# Power.net
KiCad netlist of a schematic drawn in Altium Designer
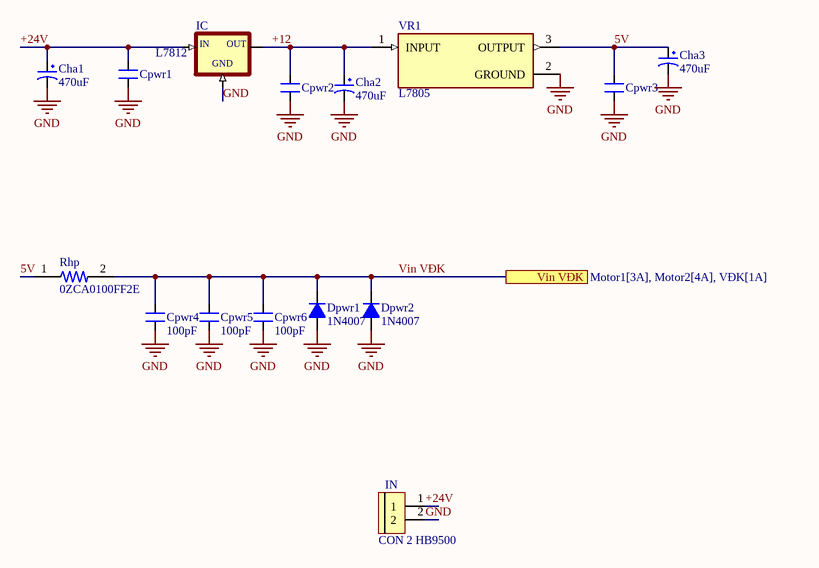
[diagram p0: Power.SchDoc]

(export (version "E")
  (design (tool "Eeschema 10.0.6"))
  (components
    (comp (ref "Cha1")
      (value "470uF")
      (footprint "CP1.5/3.4")
      (description "Cap 1000uF/16V - 220uF/50V")
      (libsource (lib "SCH_Lib_Devzone") (part "CP4"))
    )
    (comp (ref "Cha2")
      (value "470uF")
      (footprint "CP1.5/3.4")
      (description "Cap 1000uF/16V - 220uF/50V")
      (libsource (lib "SCH_Lib_Devzone") (part "CP4"))
    )
    (comp (ref "Cha3")
      (value "470uF")
      (footprint "CP1.5/3.4")
      (description "Cap 1000uF/16V - 220uF/50V")
      (libsource (lib "SCH_Lib_Devzone") (part "CP4"))
    )
    (comp (ref "Cpwr1")
      (value "100pF")
      (footprint "CN1")
      (description "Cap np  1pF - 472pF")
      (libsource (lib "SCH_Lib_Devzone") (part "CN1"))
    )
    (comp (ref "Cpwr2")
      (value "100pF")
      (footprint "CN1")
      (description "Cap np  1pF - 472pF")
      (libsource (lib "SCH_Lib_Devzone") (part "CN1"))
    )
    (comp (ref "Cpwr3")
      (value "100pF")
      (footprint "CN1")
      (description "Cap np  1pF - 472pF")
      (libsource (lib "SCH_Lib_Devzone") (part "CN1"))
    )
    (comp (ref "Cpwr4")
      (value "100pF")
      (footprint "CN1")
      (description "Cap np  1pF - 472pF")
      (libsource (lib "SCH_Lib_Devzone") (part "CN1"))
    )
    (comp (ref "Cpwr5")
      (value "100pF")
      (footprint "CN1")
      (description "Cap np  1pF - 472pF")
      (libsource (lib "SCH_Lib_Devzone") (part "CN1"))
    )
    (comp (ref "Cpwr6")
      (value "100pF")
      (footprint "CN1")
      (description "Cap np  1pF - 472pF")
      (libsource (lib "SCH_Lib_Devzone") (part "CN1"))
    )
    (comp (ref "Dpwr1")
      (value "1N4007")
      (footprint "D0.5A")
      (description "Diode 1A")
      (libsource (lib "SCH_Lib_Devzone") (part "D1A"))
    )
    (comp (ref "Dpwr2")
      (value "1N4007")
      (footprint "D0.5A")
      (description "Diode 1A")
      (libsource (lib "SCH_Lib_Devzone") (part "D1A"))
    )
    (comp (ref "IC")
      (value "L7812")
      (footprint "78XXS")
      (description "Linear Voltage Regulator IC 1 Output 1.5A D2PAK")
      (fields (field (name "MF") "STMicroelectronics"))
      (libsource (lib "L7812") (part "L7812"))
    )
    (comp (ref "IN")
      (value "CON 2 HB9500")
      (footprint "CON 2 HB9500")
      (description "Cắm")
      (libsource (lib "Altium_Lib_by_KhueNguyenCreator") (part "CON 2 HB9500"))
    )
    (comp (ref "Rhp")
      (value "0ZCA0100FF2E")
      (footprint "RESC3216X125N")
      (description "Polymeric PTC Resettable Fuse 6V 1 A Ih Surface Mount 1206 (3216 Metric), Concave")
      (fields (field (name "MF") "Bel Fuse"))
      (libsource (lib "0ZCA0100FF2E") (part "0ZCA0100FF2E"))
    )
    (comp (ref "VR1")
      (value "L7805")
      (footprint "TO255P1020X450X2000-3")
      (description "Standard Regulator Pos 5V 1.5A 3-Pin(3+Tab) TO-220FP Tube")
      (fields (field (name "MF") "STMicroelectronics"))
      (libsource (lib "L7805") (part "L7805"))
    )
  )
  (nets
    (net (code "1") (name "/+12") (class "Default")
      (node (ref "Cha2") (pin "1") (pinfunction "1_1") (pintype "passive"))
      (node (ref "Cpwr2") (pin "1") (pinfunction "1_1") (pintype "passive"))
      (node (ref "IC") (pin "OUT") (pinfunction "OUT_OUT") (pintype "passive"))
      (node (ref "VR1") (pin "1") (pinfunction "INPUT_1") (pintype "input"))
    )
    (net (code "2") (name "/+24V") (class "Default")
      (node (ref "Cha1") (pin "1") (pinfunction "1_1") (pintype "passive"))
      (node (ref "Cpwr1") (pin "1") (pinfunction "1_1") (pintype "passive"))
      (node (ref "IC") (pin "IN") (pinfunction "IN_IN") (pintype "input"))
      (node (ref "IN") (pin "1") (pinfunction "1_1") (pintype "passive"))
    )
    (net (code "3") (name "/5V") (class "Default")
      (node (ref "Cha3") (pin "1") (pinfunction "1_1") (pintype "passive"))
      (node (ref "Cpwr3") (pin "1") (pinfunction "1_1") (pintype "passive"))
      (node (ref "Rhp") (pin "1") (pinfunction "1_1") (pintype "passive"))
      (node (ref "VR1") (pin "3") (pinfunction "OUTPUT_3") (pintype "output"))
    )
    (net (code "4") (name "/Vin VĐK") (class "Default")
      (node (ref "Cpwr4") (pin "1") (pinfunction "1_1") (pintype "passive"))
      (node (ref "Cpwr5") (pin "1") (pinfunction "1_1") (pintype "passive"))
      (node (ref "Cpwr6") (pin "1") (pinfunction "1_1") (pintype "passive"))
      (node (ref "Dpwr1") (pin "2") (pinfunction "K_2") (pintype "passive"))
      (node (ref "Dpwr2") (pin "2") (pinfunction "K_2") (pintype "passive"))
      (node (ref "Rhp") (pin "2") (pinfunction "2_2") (pintype "passive"))
    )
    (net (code "5") (name "GND") (class "Default")
      (node (ref "Cha1") (pin "2") (pinfunction "2_2") (pintype "passive"))
      (node (ref "Cha2") (pin "2") (pinfunction "2_2") (pintype "passive"))
      (node (ref "Cha3") (pin "2") (pinfunction "2_2") (pintype "passive"))
      (node (ref "Cpwr1") (pin "2") (pinfunction "2_2") (pintype "passive"))
      (node (ref "Cpwr2") (pin "2") (pinfunction "2_2") (pintype "passive"))
      (node (ref "Cpwr3") (pin "2") (pinfunction "2_2") (pintype "passive"))
      (node (ref "Cpwr4") (pin "2") (pinfunction "2_2") (pintype "passive"))
      (node (ref "Cpwr5") (pin "2") (pinfunction "2_2") (pintype "passive"))
      (node (ref "Cpwr6") (pin "2") (pinfunction "2_2") (pintype "passive"))
      (node (ref "Dpwr1") (pin "1") (pinfunction "A_1") (pintype "passive"))
      (node (ref "Dpwr2") (pin "1") (pinfunction "A_1") (pintype "passive"))
      (node (ref "IC") (pin "GND") (pinfunction "GND_GND") (pintype "input"))
      (node (ref "IN") (pin "2") (pinfunction "2_2") (pintype "passive"))
      (node (ref "VR1") (pin "2") (pinfunction "GROUND_2") (pintype "power_in"))
    )
  )
)
